# bottoni.net
KiCad netlist of a schematic drawn in EAGLE
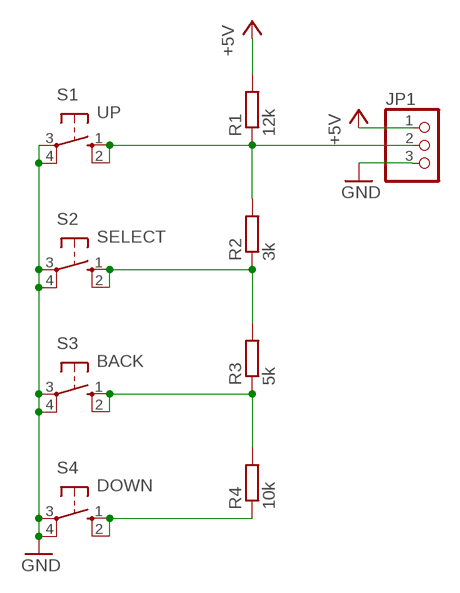
[diagram p0: schematic, sheet 1]

(export (version "E")
  (design (tool "Eeschema 10.0.6"))
  (components
    (comp (ref "JP1")
      (value "PINHD-1X3/90")
      (footprint "eagle-import:1X03_90")
      (libsource (lib "eagle-import") (part "PINHD-1X3/90"))
    )
    (comp (ref "R1")
      (value "12k")
      (footprint "eagle-import:0207_10")
      (libsource (lib "eagle-import") (part "R-EU_0207/10"))
    )
    (comp (ref "R2")
      (value "3k")
      (footprint "eagle-import:0207_10")
      (libsource (lib "eagle-import") (part "R-EU_0207/10"))
    )
    (comp (ref "R3")
      (value "5k")
      (footprint "eagle-import:0207_10")
      (libsource (lib "eagle-import") (part "R-EU_0207/10"))
    )
    (comp (ref "R4")
      (value "10k")
      (footprint "eagle-import:0207_10")
      (libsource (lib "eagle-import") (part "R-EU_0207/10"))
    )
    (comp (ref "S1")
      (value "UP")
      (footprint "eagle-import:B3F-10XX")
      (fields (field (name "MPN") "B3F-1000"))
      (libsource (lib "eagle-import") (part "10-XX"))
    )
    (comp (ref "S2")
      (value "SELECT")
      (footprint "eagle-import:B3F-10XX")
      (fields (field (name "MPN") "B3F-1000"))
      (libsource (lib "eagle-import") (part "10-XX"))
    )
    (comp (ref "S3")
      (value "BACK")
      (footprint "eagle-import:B3F-10XX")
      (fields (field (name "MPN") "B3F-1000"))
      (libsource (lib "eagle-import") (part "10-XX"))
    )
    (comp (ref "S4")
      (value "DOWN")
      (footprint "eagle-import:B3F-10XX")
      (fields (field (name "MPN") "B3F-1000"))
      (libsource (lib "eagle-import") (part "10-XX"))
    )
  )
  (nets
    (net (code "1") (name "+5V") (class "Default")
      (node (ref "JP1") (pin "1") (pinfunction "1_1") (pintype "passive"))
      (node (ref "R1") (pin "2") (pinfunction "2_2") (pintype "passive"))
    )
    (net (code "2") (name "GND") (class "Default")
      (node (ref "JP1") (pin "3") (pinfunction "3_3") (pintype "passive"))
      (node (ref "S1") (pin "3") (pinfunction "P_3") (pintype "passive"))
      (node (ref "S1") (pin "4") (pinfunction "P1_4") (pintype "passive"))
      (node (ref "S2") (pin "3") (pinfunction "P_3") (pintype "passive"))
      (node (ref "S2") (pin "4") (pinfunction "P1_4") (pintype "passive"))
      (node (ref "S3") (pin "3") (pinfunction "P_3") (pintype "passive"))
      (node (ref "S3") (pin "4") (pinfunction "P1_4") (pintype "passive"))
      (node (ref "S4") (pin "3") (pinfunction "P_3") (pintype "passive"))
      (node (ref "S4") (pin "4") (pinfunction "P1_4") (pintype "passive"))
    )
    (net (code "3") (name "Net-(S1-S)") (class "Default")
      (node (ref "JP1") (pin "2") (pinfunction "2_2") (pintype "passive"))
      (node (ref "R1") (pin "1") (pinfunction "1_1") (pintype "passive"))
      (node (ref "R2") (pin "2") (pinfunction "2_2") (pintype "passive"))
      (node (ref "S1") (pin "1") (pinfunction "S_1") (pintype "passive"))
      (node (ref "S1") (pin "2") (pinfunction "S1_2") (pintype "passive"))
    )
    (net (code "4") (name "Net-(S2-S)") (class "Default")
      (node (ref "R2") (pin "1") (pinfunction "1_1") (pintype "passive"))
      (node (ref "R3") (pin "2") (pinfunction "2_2") (pintype "passive"))
      (node (ref "S2") (pin "1") (pinfunction "S_1") (pintype "passive"))
      (node (ref "S2") (pin "2") (pinfunction "S1_2") (pintype "passive"))
    )
    (net (code "5") (name "Net-(S3-S)") (class "Default")
      (node (ref "R3") (pin "1") (pinfunction "1_1") (pintype "passive"))
      (node (ref "R4") (pin "2") (pinfunction "2_2") (pintype "passive"))
      (node (ref "S3") (pin "1") (pinfunction "S_1") (pintype "passive"))
      (node (ref "S3") (pin "2") (pinfunction "S1_2") (pintype "passive"))
    )
    (net (code "6") (name "Net-(S4-S)") (class "Default")
      (node (ref "R4") (pin "1") (pinfunction "1_1") (pintype "passive"))
      (node (ref "S4") (pin "1") (pinfunction "S_1") (pintype "passive"))
      (node (ref "S4") (pin "2") (pinfunction "S1_2") (pintype "passive"))
    )
  )
)
